# ALog-Shield.net
KiCad netlist of a schematic drawn in EAGLE
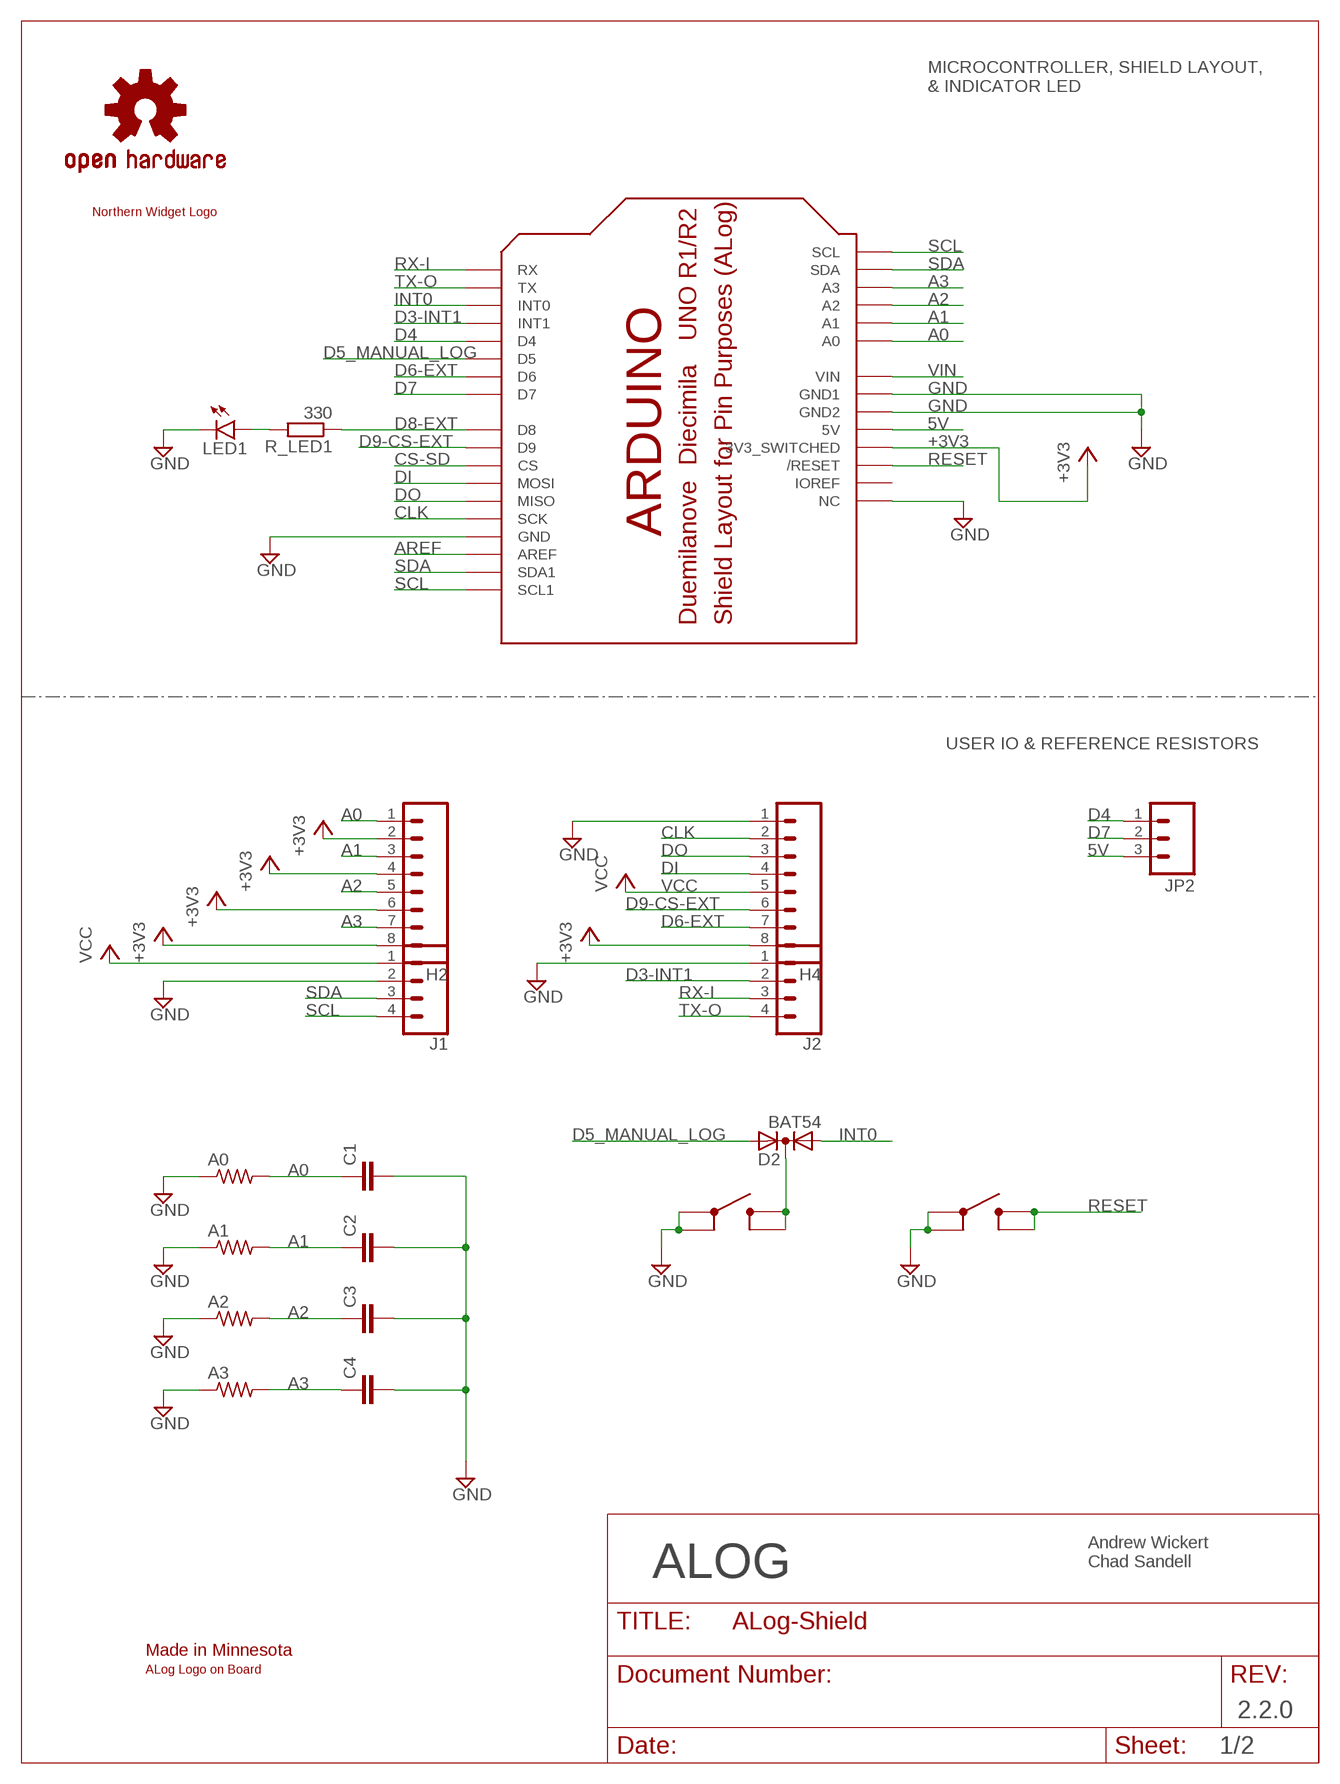
[diagram p0: schematic, sheet 1]
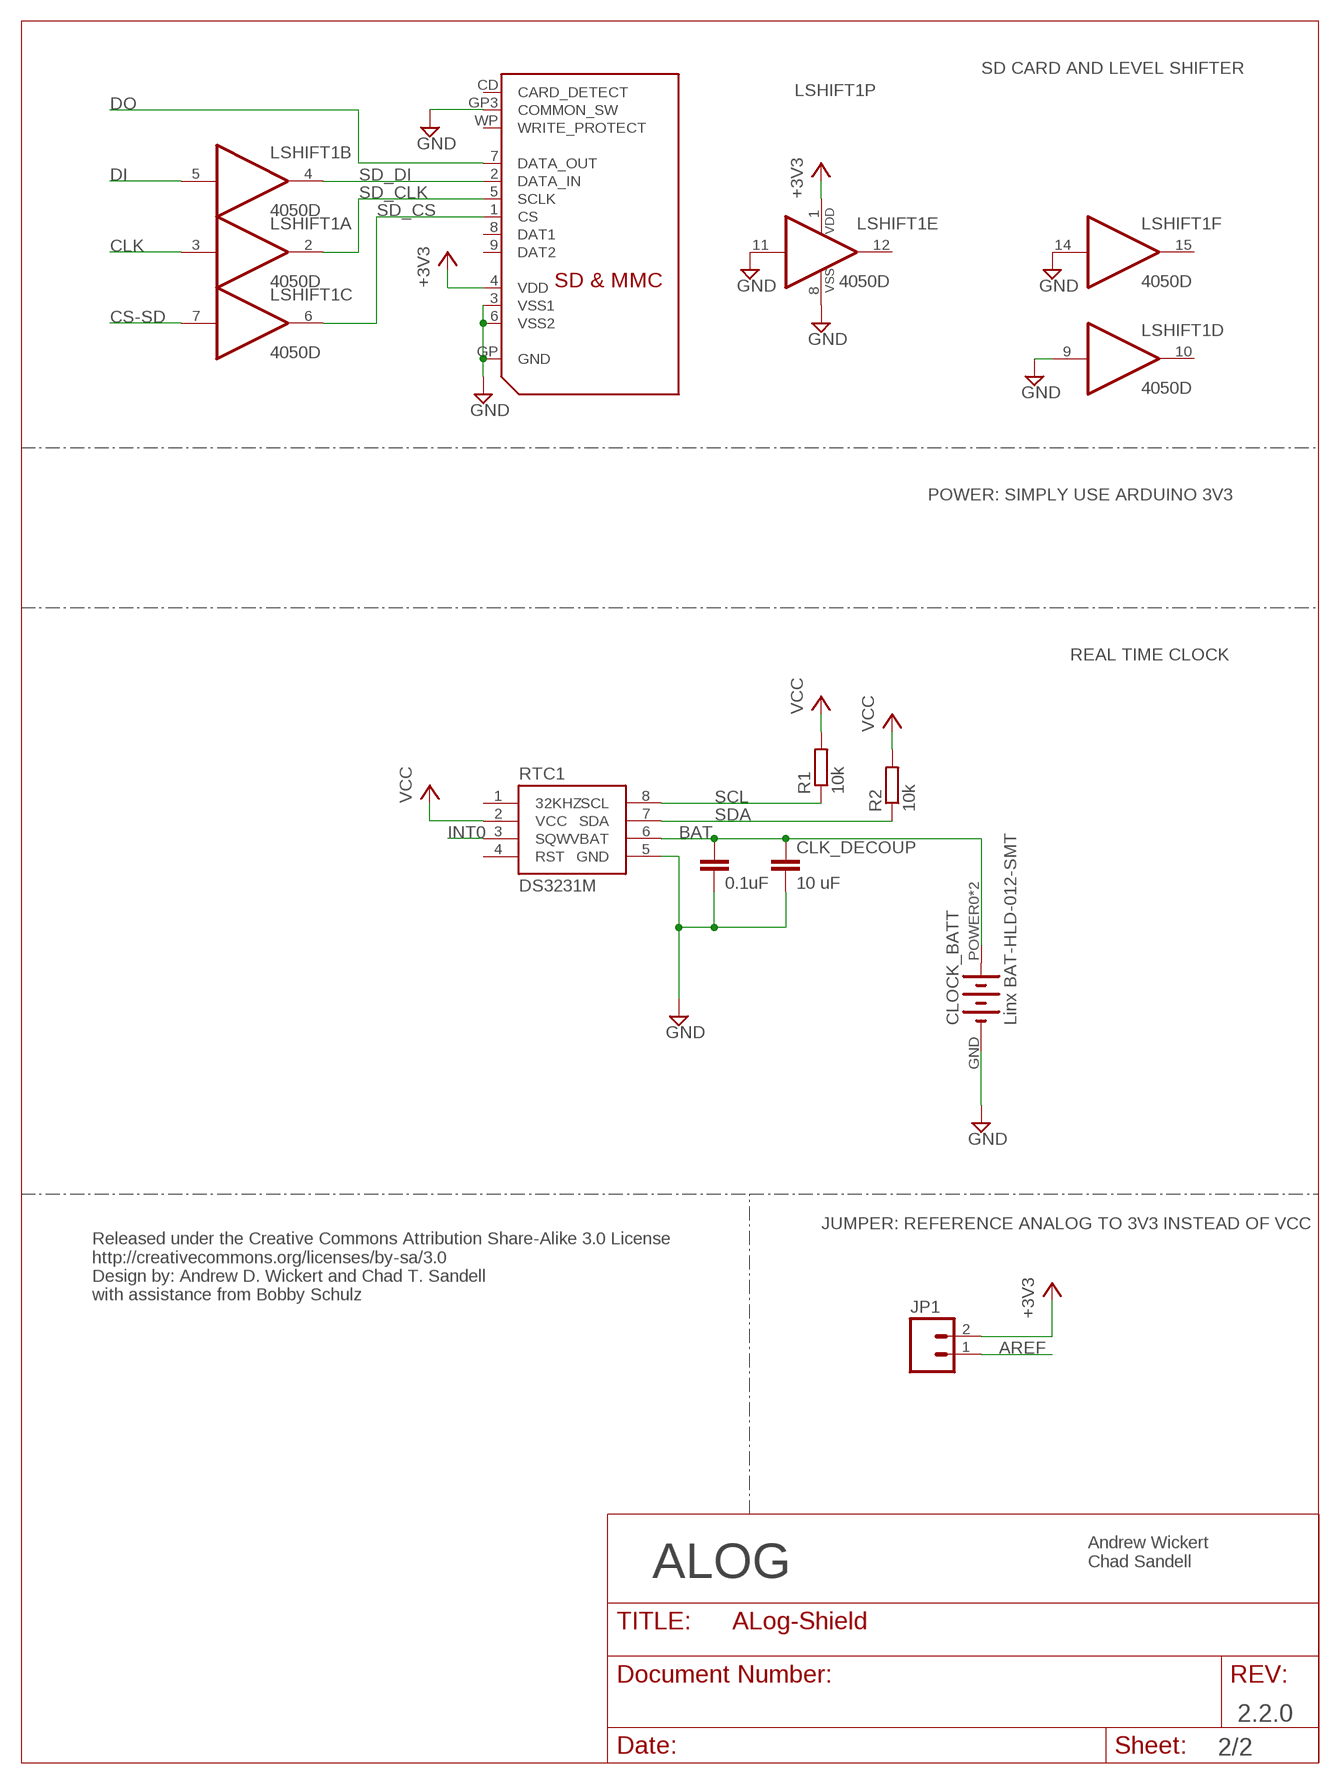
[diagram p1: schematic, sheet 2]

(export (version "E")
  (design (tool "Eeschema 10.0.6"))
  (components
    (comp (ref "A0")
      (value "R-US_0207/10")
      (footprint "eagle-import:0207_10")
      (libsource (lib "eagle-import") (part "R-US_0207/10"))
    )
    (comp (ref "A1")
      (value "R-US_0207/10")
      (footprint "eagle-import:0207_10")
      (libsource (lib "eagle-import") (part "R-US_0207/10"))
    )
    (comp (ref "A2")
      (value "R-US_0207/10")
      (footprint "eagle-import:0207_10")
      (libsource (lib "eagle-import") (part "R-US_0207/10"))
    )
    (comp (ref "A3")
      (value "R-US_0207/10")
      (footprint "eagle-import:0207_10")
      (libsource (lib "eagle-import") (part "R-US_0207/10"))
    )
    (comp (ref "C1")
      (value "C-EU0.1UFC0603")
      (footprint "eagle-import:C0603")
      (fields (field (name "MF") "Samsung") (field (name "MPN") "CL10B104KO8NNNC"))
      (libsource (lib "eagle-import") (part "C-EUC06030.1UF"))
    )
    (comp (ref "C2")
      (value "C-EU0.1UFC0603")
      (footprint "eagle-import:C0603")
      (fields (field (name "MF") "Samsung") (field (name "MPN") "CL10B104KO8NNNC"))
      (libsource (lib "eagle-import") (part "C-EUC06030.1UF"))
    )
    (comp (ref "C3")
      (value "C-EU0.1UFC0603")
      (footprint "eagle-import:C0603")
      (fields (field (name "MF") "Samsung") (field (name "MPN") "CL10B104KO8NNNC"))
      (libsource (lib "eagle-import") (part "C-EUC06030.1UF"))
    )
    (comp (ref "C4")
      (value "C-EU0.1UFC0603")
      (footprint "eagle-import:C0603")
      (fields (field (name "MF") "Samsung") (field (name "MPN") "CL10B104KO8NNNC"))
      (libsource (lib "eagle-import") (part "C-EUC06030.1UF"))
    )
    (comp (ref "D2")
      (value "BAT54")
      (footprint "eagle-import:SOT23C")
      (libsource (lib "eagle-import") (part "DIODE_AC-CA_"))
    )
    (comp (ref "H2")
      (value "M083.5MM-8")
      (footprint "eagle-import:SCREWTERMINAL-3.5MM-8")
      (libsource (lib "eagle-import") (part "M083.5MM-8"))
    )
    (comp (ref "H4")
      (value "M083.5MM-8")
      (footprint "eagle-import:SCREWTERMINAL-3.5MM-8")
      (libsource (lib "eagle-import") (part "M083.5MM-8"))
    )
    (comp (ref "J1")
      (value "CONN_04SCREW")
      (footprint "eagle-import:SCREWTERMINAL-3.5MM-4")
      (libsource (lib "eagle-import") (part "CONN_04SCREW"))
    )
    (comp (ref "J2")
      (value "CONN_04SCREW")
      (footprint "eagle-import:SCREWTERMINAL-3.5MM-4")
      (libsource (lib "eagle-import") (part "CONN_04SCREW"))
    )
    (comp (ref "JP2")
      (value "M03SCREW")
      (footprint "eagle-import:SCREWTERMINAL-3.5MM-3")
      (libsource (lib "eagle-import") (part "M03SCREW"))
    )
    (comp (ref "LED1")
      (value "LED1206")
      (footprint "eagle-import:LED-1206")
      (libsource (lib "eagle-import") (part "LED1206"))
    )
    (comp (ref "LOG")
      (value "LOG")
      (footprint "eagle-import:SWITCH_4.2X3.2")
      (libsource (lib "eagle-import") (part "BUTTON4.2X3.2"))
    )
    (comp (ref "LOGO1")
      (value "OSHW-LOGOL")
      (footprint "eagle-import:OSHW-LOGO-L")
      (libsource (lib "eagle-import") (part "OSHW-LOGOL"))
    )
    (comp (ref "RESET")
      (value "Reset")
      (footprint "eagle-import:SWITCH_4.2X3.2")
      (libsource (lib "eagle-import") (part "BUTTON4.2X3.2"))
    )
    (comp (ref "R_LED1")
      (value "330")
      (footprint "eagle-import:R0603")
      (fields (field (name "MF") "Yageo") (field (name "MPN") "RC0603FR-07330RL"))
      (libsource (lib "eagle-import") (part "bschulz_passives_R-EU_R0603330"))
    )
    (comp (ref "U$1")
      (value "NWLOGO_MED")
      (footprint "eagle-import:NWLOGO_MED")
      (libsource (lib "eagle-import") (part "NWLOGO_MED"))
    )
    (comp (ref "U$2")
      (value "MADE_IN_MN_220_SHIELD")
      (footprint "eagle-import:MADE_IN_MN_SHIELD_220")
      (libsource (lib "eagle-import") (part "MADE_IN_MN_220_SHIELD"))
    )
    (comp (ref "U$3")
      (value "ALOG_LOG")
      (footprint "eagle-import:ALOG_LOG")
      (libsource (lib "eagle-import") (part "ALOG_LOG"))
    )
    (comp (ref "U$9")
      (value "AWICKERT_ARDUINO_SHIELD_PIN_PURPOSE")
      (footprint "eagle-import:AWICKERT_ARDUINO_SHIELD_PINS_ONLY")
      (libsource (lib "eagle-import") (part "AWICKERT_ARDUINO_SHIELD_PIN_PURPOSE"))
    )
    (comp (ref "CLK_DECOUP")
      (value "10 uF")
      (footprint "eagle-import:C0805")
      (fields (field (name "MF") "Samsung") (field (name "MPN") "CL21A106KQCLRNC"))
      (libsource (lib "eagle-import") (part "C-EUC080510UF"))
    )
    (comp (ref "CLOCK_BATT")
      (value "Linx BAT-HLD-012-SMT")
      (footprint "eagle-import:LINX_BAT-HLD-012-SMT")
      (libsource (lib "eagle-import") (part "LINX-BAT-HLD-012-SMT-OTL"))
    )
    (comp (ref "CLOCK_BATT_DECOUP")
      (value "0.1uF")
      (footprint "eagle-import:C0603")
      (fields (field (name "MF") "Samsung") (field (name "MPN") "CL10B104KO8NNNC"))
      (libsource (lib "eagle-import") (part "C-EUC06030.1UF"))
    )
    (comp (ref "JP1")
      (value "M02LOCK")
      (footprint "eagle-import:1X02_LOCK")
      (libsource (lib "eagle-import") (part "M02LOCK"))
    )
    (comp (ref "LSHIFT1")
      (value "4050D")
      (footprint "eagle-import:SO16")
      (libsource (lib "eagle-import") (part "4050D"))
    )
    (comp (ref "R1")
      (value "10k")
      (footprint "eagle-import:R0603")
      (libsource (lib "eagle-import") (part "R-EU_R0603"))
    )
    (comp (ref "R2")
      (value "10k")
      (footprint "eagle-import:R0603")
      (libsource (lib "eagle-import") (part "R-EU_R0603"))
    )
    (comp (ref "RTC1")
      (value "DS3231M")
      (footprint "eagle-import:SO08")
      (fields (field (name "MF") "Maxim") (field (name "MPN") "DS3231MZ+"))
      (libsource (lib "eagle-import") (part "DS3231M"))
    )
    (comp (ref "SD1")
      (value "SDMMC06132")
      (footprint "eagle-import:06132")
      (libsource (lib "eagle-import") (part "SDMMC06132"))
    )
  )
  (nets
    (net (code "1") (name "+3V3") (class "Default")
      (node (ref "H2") (pin "2") (pinfunction "2_2") (pintype "passive"))
      (node (ref "H2") (pin "4") (pinfunction "4_4") (pintype "passive"))
      (node (ref "H2") (pin "6") (pinfunction "6_6") (pintype "passive"))
      (node (ref "H2") (pin "8") (pinfunction "8_8") (pintype "passive"))
      (node (ref "H4") (pin "8") (pinfunction "8_8") (pintype "passive"))
      (node (ref "JP1") (pin "2") (pinfunction "2_2") (pintype "passive"))
      (node (ref "LSHIFT1") (pin "1") (pinfunction "VDD_1") (pintype "power_in"))
      (node (ref "SD1") (pin "4") (pinfunction "VDD_4") (pintype "power_in"))
      (node (ref "U$9") (pin "3.3V") (pinfunction "3V3_SWITCHED_3.3V") (pintype "power_in"))
    )
    (net (code "2") (name "5V") (class "Default")
      (node (ref "JP2") (pin "3") (pinfunction "3_3") (pintype "passive"))
      (node (ref "U$9") (pin "5V") (pinfunction "5V_5V") (pintype "power_in"))
    )
    (net (code "3") (name "A0") (class "Default")
      (node (ref "A0") (pin "2") (pinfunction "2_2") (pintype "passive"))
      (node (ref "C1") (pin "1") (pinfunction "1_1") (pintype "passive"))
      (node (ref "H2") (pin "1") (pinfunction "1_1") (pintype "passive"))
      (node (ref "U$9") (pin "A0") (pinfunction "A0_A0") (pintype "bidirectional"))
    )
    (net (code "4") (name "A1") (class "Default")
      (node (ref "A1") (pin "2") (pinfunction "2_2") (pintype "passive"))
      (node (ref "C2") (pin "1") (pinfunction "1_1") (pintype "passive"))
      (node (ref "H2") (pin "3") (pinfunction "3_3") (pintype "passive"))
      (node (ref "U$9") (pin "A1") (pinfunction "A1_A1") (pintype "bidirectional"))
    )
    (net (code "5") (name "A2") (class "Default")
      (node (ref "A2") (pin "2") (pinfunction "2_2") (pintype "passive"))
      (node (ref "C3") (pin "1") (pinfunction "1_1") (pintype "passive"))
      (node (ref "H2") (pin "5") (pinfunction "5_5") (pintype "passive"))
      (node (ref "U$9") (pin "A2") (pinfunction "A2_A2") (pintype "bidirectional"))
    )
    (net (code "6") (name "A3") (class "Default")
      (node (ref "A3") (pin "2") (pinfunction "2_2") (pintype "passive"))
      (node (ref "C4") (pin "1") (pinfunction "1_1") (pintype "passive"))
      (node (ref "H2") (pin "7") (pinfunction "7_7") (pintype "passive"))
      (node (ref "U$9") (pin "A3") (pinfunction "A3_A3") (pintype "bidirectional"))
    )
    (net (code "7") (name "AREF") (class "Default")
      (node (ref "JP1") (pin "1") (pinfunction "1_1") (pintype "passive"))
      (node (ref "U$9") (pin "AREF") (pinfunction "AREF_AREF") (pintype "bidirectional"))
    )
    (net (code "8") (name "BAT") (class "Default")
      (node (ref "CLK_DECOUP") (pin "1") (pinfunction "1_1") (pintype "passive"))
      (node (ref "CLOCK_BATT") (pin "POWER0") (pinfunction "+_POWER0") (pintype "passive"))
      (node (ref "CLOCK_BATT") (pin "POWER1") (pinfunction "+_POWER1") (pintype "passive"))
      (node (ref "CLOCK_BATT_DECOUP") (pin "1") (pinfunction "1_1") (pintype "passive"))
      (node (ref "RTC1") (pin "6") (pinfunction "VBAT_6") (pintype "power_in"))
    )
    (net (code "9") (name "CLK") (class "Default")
      (node (ref "H4") (pin "2") (pinfunction "2_2") (pintype "passive"))
      (node (ref "LSHIFT1") (pin "3") (pinfunction "I_3") (pintype "input"))
      (node (ref "U$9") (pin "D13") (pinfunction "SCK_D13") (pintype "bidirectional"))
    )
    (net (code "10") (name "CS-SD") (class "Default")
      (node (ref "LSHIFT1") (pin "7") (pinfunction "I_7") (pintype "input"))
      (node (ref "U$9") (pin "D10") (pinfunction "CS_D10") (pintype "bidirectional"))
    )
    (net (code "11") (name "D3-INT1") (class "Default")
      (node (ref "J2") (pin "2") (pinfunction "2_2") (pintype "passive"))
      (node (ref "U$9") (pin "D3") (pinfunction "INT1_D3") (pintype "bidirectional"))
    )
    (net (code "12") (name "D4") (class "Default")
      (node (ref "JP2") (pin "1") (pinfunction "1_1") (pintype "passive"))
      (node (ref "U$9") (pin "D4") (pinfunction "D4_D4") (pintype "bidirectional"))
    )
    (net (code "13") (name "D5_MANUAL_LOG") (class "Default")
      (node (ref "D2") (pin "2") (pinfunction "A2_2") (pintype "passive"))
      (node (ref "U$9") (pin "D5") (pinfunction "D5_D5") (pintype "bidirectional"))
    )
    (net (code "14") (name "D6-EXT") (class "Default")
      (node (ref "H4") (pin "7") (pinfunction "7_7") (pintype "passive"))
      (node (ref "U$9") (pin "D6") (pinfunction "D6_D6") (pintype "bidirectional"))
    )
    (net (code "15") (name "D7") (class "Default")
      (node (ref "JP2") (pin "2") (pinfunction "2_2") (pintype "passive"))
      (node (ref "U$9") (pin "D7") (pinfunction "D7_D7") (pintype "bidirectional"))
    )
    (net (code "16") (name "D8-EXT") (class "Default")
      (node (ref "R_LED1") (pin "1") (pinfunction "1_1") (pintype "passive"))
      (node (ref "U$9") (pin "D8") (pinfunction "D8_D8") (pintype "bidirectional"))
    )
    (net (code "17") (name "D9-CS-EXT") (class "Default")
      (node (ref "H4") (pin "6") (pinfunction "6_6") (pintype "passive"))
      (node (ref "U$9") (pin "D9") (pinfunction "D9_D9") (pintype "bidirectional"))
    )
    (net (code "18") (name "DI") (class "Default")
      (node (ref "H4") (pin "4") (pinfunction "4_4") (pintype "passive"))
      (node (ref "LSHIFT1") (pin "5") (pinfunction "I_5") (pintype "input"))
      (node (ref "U$9") (pin "D11") (pinfunction "MOSI_D11") (pintype "bidirectional"))
    )
    (net (code "19") (name "DO") (class "Default")
      (node (ref "H4") (pin "3") (pinfunction "3_3") (pintype "passive"))
      (node (ref "SD1") (pin "7") (pinfunction "DATA_OUT_7") (pintype "output"))
      (node (ref "U$9") (pin "D12") (pinfunction "MISO_D12") (pintype "bidirectional"))
    )
    (net (code "20") (name "GND") (class "Default")
      (node (ref "A0") (pin "1") (pinfunction "1_1") (pintype "passive"))
      (node (ref "A1") (pin "1") (pinfunction "1_1") (pintype "passive"))
      (node (ref "A2") (pin "1") (pinfunction "1_1") (pintype "passive"))
      (node (ref "A3") (pin "1") (pinfunction "1_1") (pintype "passive"))
      (node (ref "C1") (pin "2") (pinfunction "2_2") (pintype "passive"))
      (node (ref "C2") (pin "2") (pinfunction "2_2") (pintype "passive"))
      (node (ref "C3") (pin "2") (pinfunction "2_2") (pintype "passive"))
      (node (ref "C4") (pin "2") (pinfunction "2_2") (pintype "passive"))
      (node (ref "CLK_DECOUP") (pin "2") (pinfunction "2_2") (pintype "passive"))
      (node (ref "CLOCK_BATT") (pin "GND") (pinfunction "-_GND") (pintype "passive"))
      (node (ref "CLOCK_BATT_DECOUP") (pin "2") (pinfunction "2_2") (pintype "passive"))
      (node (ref "H4") (pin "1") (pinfunction "1_1") (pintype "passive"))
      (node (ref "J1") (pin "2") (pinfunction "2_2") (pintype "passive"))
      (node (ref "J2") (pin "1") (pinfunction "1_1") (pintype "passive"))
      (node (ref "LED1") (pin "C") (pinfunction "C_C") (pintype "passive"))
      (node (ref "LOG") (pin "1") (pinfunction "1_1") (pintype "bidirectional"))
      (node (ref "LOG") (pin "2") (pinfunction "2_2") (pintype "bidirectional"))
      (node (ref "LSHIFT1") (pin "11") (pinfunction "I_11") (pintype "input"))
      (node (ref "LSHIFT1") (pin "14") (pinfunction "I_14") (pintype "input"))
      (node (ref "LSHIFT1") (pin "8") (pinfunction "VSS_8") (pintype "power_in"))
      (node (ref "LSHIFT1") (pin "9") (pinfunction "I_9") (pintype "input"))
      (node (ref "RESET") (pin "1") (pinfunction "1_1") (pintype "bidirectional"))
      (node (ref "RESET") (pin "2") (pinfunction "2_2") (pintype "bidirectional"))
      (node (ref "RTC1") (pin "5") (pinfunction "GND_5") (pintype "power_in"))
      (node (ref "SD1") (pin "3") (pinfunction "VSS1_3") (pintype "power_in"))
      (node (ref "SD1") (pin "6") (pinfunction "VSS2_6") (pintype "power_in"))
      (node (ref "SD1") (pin "GP") (pinfunction "GND_GP") (pintype "power_in"))
      (node (ref "SD1") (pin "GP3") (pinfunction "COMMON_SW_GP3") (pintype "passive"))
      (node (ref "U$9") (pin "GND@0") (pinfunction "GND_GND@0") (pintype "power_in"))
      (node (ref "U$9") (pin "GND@1") (pinfunction "GND1_GND@1") (pintype "power_in"))
      (node (ref "U$9") (pin "GND@2") (pinfunction "GND2_GND@2") (pintype "power_in"))
      (node (ref "U$9") (pin "NC") (pinfunction "NC_NC") (pintype "bidirectional"))
    )
    (net (code "21") (name "INT0") (class "Default")
      (node (ref "D2") (pin "1") (pinfunction "A1_1") (pintype "passive"))
      (node (ref "RTC1") (pin "3") (pinfunction "SQW_3") (pintype "output"))
      (node (ref "U$9") (pin "D2") (pinfunction "INT0_D2") (pintype "bidirectional"))
    )
    (net (code "22") (name "Net-(D2-K)") (class "Default")
      (node (ref "D2") (pin "3") (pinfunction "K_3") (pintype "passive"))
      (node (ref "LOG") (pin "3") (pinfunction "4_3") (pintype "bidirectional"))
      (node (ref "LOG") (pin "4") (pinfunction "3_4") (pintype "bidirectional"))
    )
    (net (code "23") (name "Net-(LED1-PadA)") (class "Default")
      (node (ref "LED1") (pin "A") (pinfunction "A_A") (pintype "passive"))
      (node (ref "R_LED1") (pin "2") (pinfunction "2_2") (pintype "passive"))
    )
    (net (code "24") (name "RESET") (class "Default")
      (node (ref "RESET") (pin "3") (pinfunction "4_3") (pintype "bidirectional"))
      (node (ref "RESET") (pin "4") (pinfunction "3_4") (pintype "bidirectional"))
      (node (ref "U$9") (pin "RES") (pinfunction "/RESET_RES") (pintype "bidirectional"))
    )
    (net (code "25") (name "RX-I") (class "Default")
      (node (ref "J2") (pin "3") (pinfunction "3_3") (pintype "passive"))
      (node (ref "U$9") (pin "RX") (pinfunction "RX_RX") (pintype "bidirectional"))
    )
    (net (code "26") (name "SCL") (class "Default")
      (node (ref "J1") (pin "4") (pinfunction "4_4") (pintype "passive"))
      (node (ref "R1") (pin "1") (pinfunction "1_1") (pintype "passive"))
      (node (ref "RTC1") (pin "8") (pinfunction "SCL_8") (pintype "bidirectional"))
      (node (ref "U$9") (pin "A5") (pinfunction "SCL_A5") (pintype "bidirectional"))
      (node (ref "U$9") (pin "SCL") (pinfunction "SCL1_SCL") (pintype "bidirectional"))
    )
    (net (code "27") (name "SDA") (class "Default")
      (node (ref "J1") (pin "3") (pinfunction "3_3") (pintype "passive"))
      (node (ref "R2") (pin "1") (pinfunction "1_1") (pintype "passive"))
      (node (ref "RTC1") (pin "7") (pinfunction "SDA_7") (pintype "bidirectional"))
      (node (ref "U$9") (pin "A4") (pinfunction "SDA_A4") (pintype "bidirectional"))
      (node (ref "U$9") (pin "SDA") (pinfunction "SDA1_SDA") (pintype "bidirectional"))
    )
    (net (code "28") (name "SD_CLK") (class "Default")
      (node (ref "LSHIFT1") (pin "2") (pinfunction "O_2") (pintype "output"))
      (node (ref "SD1") (pin "5") (pinfunction "SCLK_5") (pintype "input"))
    )
    (net (code "29") (name "SD_CS") (class "Default")
      (node (ref "LSHIFT1") (pin "6") (pinfunction "O_6") (pintype "output"))
      (node (ref "SD1") (pin "1") (pinfunction "CS_1") (pintype "input"))
    )
    (net (code "30") (name "SD_DI") (class "Default")
      (node (ref "LSHIFT1") (pin "4") (pinfunction "O_4") (pintype "output"))
      (node (ref "SD1") (pin "2") (pinfunction "DATA_IN_2") (pintype "input"))
    )
    (net (code "31") (name "TX-O") (class "Default")
      (node (ref "J2") (pin "4") (pinfunction "4_4") (pintype "passive"))
      (node (ref "U$9") (pin "TX") (pinfunction "TX_TX") (pintype "bidirectional"))
    )
    (net (code "32") (name "VCC") (class "Default")
      (node (ref "H4") (pin "5") (pinfunction "5_5") (pintype "passive"))
      (node (ref "J1") (pin "1") (pinfunction "1_1") (pintype "passive"))
      (node (ref "R1") (pin "2") (pinfunction "2_2") (pintype "passive"))
      (node (ref "R2") (pin "2") (pinfunction "2_2") (pintype "passive"))
      (node (ref "RTC1") (pin "2") (pinfunction "VCC_2") (pintype "power_in"))
    )
    (net (code "33") (name "VIN") (class "Default")
      (node (ref "U$9") (pin "VIN") (pinfunction "VIN_VIN") (pintype "power_in"))
    )
    (net (code "34") (name "unconnected-(LSHIFT1D-O-Pad10)") (class "Default")
      (node (ref "LSHIFT1") (pin "10") (pinfunction "O_10") (pintype "output"))
    )
    (net (code "35") (name "unconnected-(LSHIFT1E-O-Pad12)") (class "Default")
      (node (ref "LSHIFT1") (pin "12") (pinfunction "O_12") (pintype "output"))
    )
    (net (code "36") (name "unconnected-(LSHIFT1F-O-Pad15)") (class "Default")
      (node (ref "LSHIFT1") (pin "15") (pinfunction "O_15") (pintype "output"))
    )
    (net (code "37") (name "unconnected-(RTC1-32KHZ-Pad1)") (class "Default")
      (node (ref "RTC1") (pin "1") (pinfunction "32KHZ_1") (pintype "output"))
    )
    (net (code "38") (name "unconnected-(RTC1-RST-Pad4)") (class "Default")
      (node (ref "RTC1") (pin "4") (pinfunction "RST_4") (pintype "bidirectional"))
    )
    (net (code "39") (name "unconnected-(SD1-CARD_DETECT-PadCD)") (class "Default")
      (node (ref "SD1") (pin "CD") (pinfunction "CARD_DETECT_CD") (pintype "passive"))
    )
    (net (code "40") (name "unconnected-(SD1-DAT1-Pad8)") (class "Default")
      (node (ref "SD1") (pin "8") (pinfunction "DAT1_8") (pintype "bidirectional"))
    )
    (net (code "41") (name "unconnected-(SD1-DAT2-Pad9)") (class "Default")
      (node (ref "SD1") (pin "9") (pinfunction "DAT2_9") (pintype "bidirectional"))
    )
    (net (code "42") (name "unconnected-(SD1-WRITE_PROTECT-PadWP)") (class "Default")
      (node (ref "SD1") (pin "WP") (pinfunction "WRITE_PROTECT_WP") (pintype "passive"))
    )
    (net (code "43") (name "unconnected-(U$9-PadIOREF)") (class "Default")
      (node (ref "U$9") (pin "IOREF") (pinfunction "IOREF_IOREF") (pintype "bidirectional"))
    )
  )
)
